# Charge_Li_ION.net
KiCad netlist of a schematic drawn in EAGLE
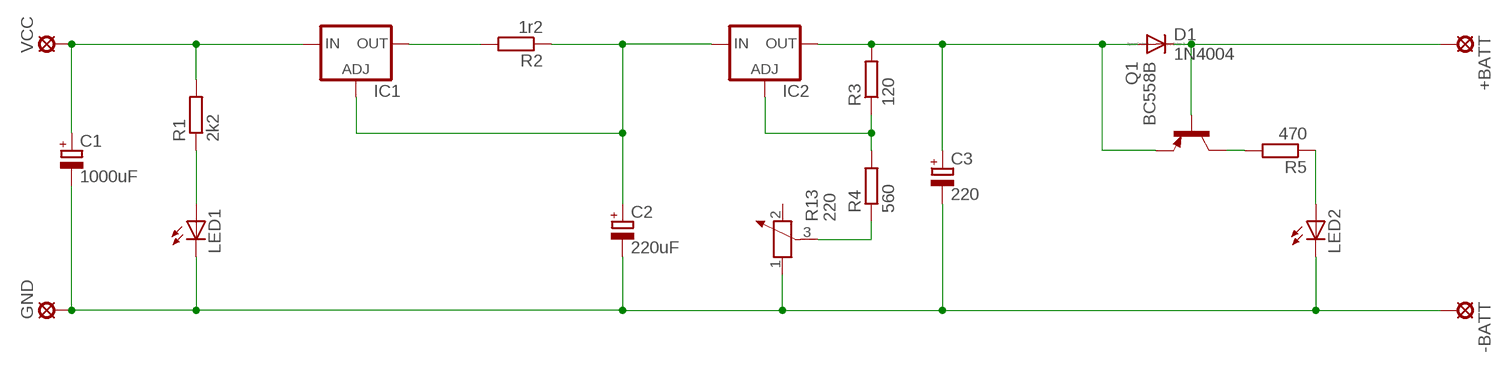
[diagram p0: schematic, sheet 1]

(export (version "E")
  (design (tool "Eeschema 10.0.6"))
  (components
    (comp (ref "+BATT")
      (value "LSP13")
      (footprint "eagle-import:LSP13")
      (libsource (lib "eagle-import") (part "LSP13"))
    )
    (comp (ref "-BATT")
      (value "LSP13")
      (footprint "eagle-import:LSP13")
      (libsource (lib "eagle-import") (part "LSP13"))
    )
    (comp (ref "C1")
      (value "1000uF")
      (footprint "eagle-import:E3,5-8")
      (libsource (lib "eagle-import") (part "CPOL-EUE3.5-8"))
    )
    (comp (ref "C2")
      (value "220uF")
      (footprint "eagle-import:E3,5-8")
      (libsource (lib "eagle-import") (part "CPOL-EUE3.5-8"))
    )
    (comp (ref "C3")
      (value "220")
      (footprint "eagle-import:E3,5-8")
      (libsource (lib "eagle-import") (part "CPOL-EUE3.5-8"))
    )
    (comp (ref "D1")
      (value "1N4004")
      (footprint "eagle-import:DO41-10")
      (libsource (lib "eagle-import") (part "1N4004"))
    )
    (comp (ref "GND")
      (value "LSP13")
      (footprint "eagle-import:LSP13")
      (libsource (lib "eagle-import") (part "LSP13"))
    )
    (comp (ref "IC1")
      (value "LM317TS")
      (footprint "eagle-import:317TS")
      (libsource (lib "eagle-import") (part "LM317TS"))
    )
    (comp (ref "IC2")
      (value "LM317TS")
      (footprint "eagle-import:317TS")
      (libsource (lib "eagle-import") (part "LM317TS"))
    )
    (comp (ref "LED1")
      (value "LED5MM")
      (footprint "eagle-import:LED5MM")
      (libsource (lib "eagle-import") (part "LED5MM"))
    )
    (comp (ref "LED2")
      (value "LED5MM")
      (footprint "eagle-import:LED5MM")
      (libsource (lib "eagle-import") (part "LED5MM"))
    )
    (comp (ref "Q1")
      (value "BC558B")
      (footprint "eagle-import:TO92-EBC")
      (libsource (lib "eagle-import") (part "BC558B"))
    )
    (comp (ref "R1")
      (value "2k2")
      (footprint "eagle-import:0207_7")
      (libsource (lib "eagle-import") (part "R-EU_0207/7"))
    )
    (comp (ref "R2")
      (value "1r2")
      (footprint "eagle-import:0207_7")
      (libsource (lib "eagle-import") (part "R-EU_0207/7"))
    )
    (comp (ref "R3")
      (value "120")
      (footprint "eagle-import:0207_7")
      (libsource (lib "eagle-import") (part "R-EU_0207/7"))
    )
    (comp (ref "R4")
      (value "560")
      (footprint "eagle-import:0207_7")
      (libsource (lib "eagle-import") (part "R-EU_0207/7"))
    )
    (comp (ref "R5")
      (value "470")
      (footprint "eagle-import:0207_7")
      (libsource (lib "eagle-import") (part "R-EU_0207/7"))
    )
    (comp (ref "R13")
      (value "220")
      (footprint "eagle-import:PT-10")
      (libsource (lib "eagle-import") (part "POTENTIOMETER_PT-10"))
    )
    (comp (ref "VCC")
      (value "LSP13")
      (footprint "eagle-import:LSP13")
      (libsource (lib "eagle-import") (part "LSP13"))
    )
  )
  (nets
    (net (code "1") (name "Net-(+BATT-PadMP)") (class "Default")
      (node (ref "+BATT") (pin "MP") (pinfunction "MP_MP") (pintype "passive"))
      (node (ref "D1") (pin "C") (pinfunction "C_C") (pintype "passive"))
      (node (ref "Q1") (pin "B") (pinfunction "B_B") (pintype "passive"))
    )
    (net (code "2") (name "Net-(IC1-ADJ)") (class "Default")
      (node (ref "C2") (pin "+") (pinfunction "+_+") (pintype "passive"))
      (node (ref "IC1") (pin "1") (pinfunction "ADJ_1") (pintype "input"))
      (node (ref "IC2") (pin "3") (pinfunction "IN_3") (pintype "input"))
      (node (ref "R2") (pin "1") (pinfunction "1_1") (pintype "passive"))
    )
    (net (code "3") (name "Net-(IC1-IN)") (class "Default")
      (node (ref "C1") (pin "+") (pinfunction "+_+") (pintype "passive"))
      (node (ref "IC1") (pin "3") (pinfunction "IN_3") (pintype "input"))
      (node (ref "R1") (pin "2") (pinfunction "2_2") (pintype "passive"))
      (node (ref "VCC") (pin "MP") (pinfunction "MP_MP") (pintype "passive"))
    )
    (net (code "4") (name "Net-(IC1-OUT)") (class "Default")
      (node (ref "IC1") (pin "2") (pinfunction "OUT_2") (pintype "passive"))
      (node (ref "R2") (pin "2") (pinfunction "2_2") (pintype "passive"))
    )
    (net (code "5") (name "Net-(IC2-ADJ)") (class "Default")
      (node (ref "IC2") (pin "1") (pinfunction "ADJ_1") (pintype "input"))
      (node (ref "R3") (pin "1") (pinfunction "1_1") (pintype "passive"))
      (node (ref "R4") (pin "2") (pinfunction "2_2") (pintype "passive"))
    )
    (net (code "6") (name "Net-(IC2-OUT)") (class "Default")
      (node (ref "C3") (pin "+") (pinfunction "+_+") (pintype "passive"))
      (node (ref "D1") (pin "A") (pinfunction "A_A") (pintype "passive"))
      (node (ref "IC2") (pin "2") (pinfunction "OUT_2") (pintype "passive"))
      (node (ref "Q1") (pin "E") (pinfunction "E_E") (pintype "passive"))
      (node (ref "R3") (pin "2") (pinfunction "2_2") (pintype "passive"))
    )
    (net (code "7") (name "Net-(LED1-C)") (class "Default")
      (node (ref "-BATT") (pin "MP") (pinfunction "MP_MP") (pintype "passive"))
      (node (ref "C1") (pin "-") (pinfunction "-_-") (pintype "passive"))
      (node (ref "C2") (pin "-") (pinfunction "-_-") (pintype "passive"))
      (node (ref "C3") (pin "-") (pinfunction "-_-") (pintype "passive"))
      (node (ref "GND") (pin "MP") (pinfunction "MP_MP") (pintype "passive"))
      (node (ref "LED1") (pin "K") (pinfunction "C_K") (pintype "passive"))
      (node (ref "LED2") (pin "K") (pinfunction "C_K") (pintype "passive"))
      (node (ref "R13") (pin "1") (pinfunction "1_1") (pintype "passive"))
    )
    (net (code "8") (name "Net-(LED1-PadA)") (class "Default")
      (node (ref "LED1") (pin "A") (pinfunction "A_A") (pintype "passive"))
      (node (ref "R1") (pin "1") (pinfunction "1_1") (pintype "passive"))
    )
    (net (code "9") (name "Net-(LED2-PadA)") (class "Default")
      (node (ref "LED2") (pin "A") (pinfunction "A_A") (pintype "passive"))
      (node (ref "R5") (pin "1") (pinfunction "1_1") (pintype "passive"))
    )
    (net (code "10") (name "Net-(Q1-PadC)") (class "Default")
      (node (ref "Q1") (pin "C") (pinfunction "C_C") (pintype "passive"))
      (node (ref "R5") (pin "2") (pinfunction "2_2") (pintype "passive"))
    )
    (net (code "11") (name "Net-(R13-Pad3)") (class "Default")
      (node (ref "R13") (pin "3") (pinfunction "3_3") (pintype "passive"))
      (node (ref "R4") (pin "1") (pinfunction "1_1") (pintype "passive"))
    )
    (net (code "12") (name "unconnected-(R13-Pad2)") (class "Default")
      (node (ref "R13") (pin "2") (pinfunction "2_2") (pintype "passive"))
    )
  )
)
